# Interfaces.net
KiCad netlist of a schematic drawn in Altium Designer
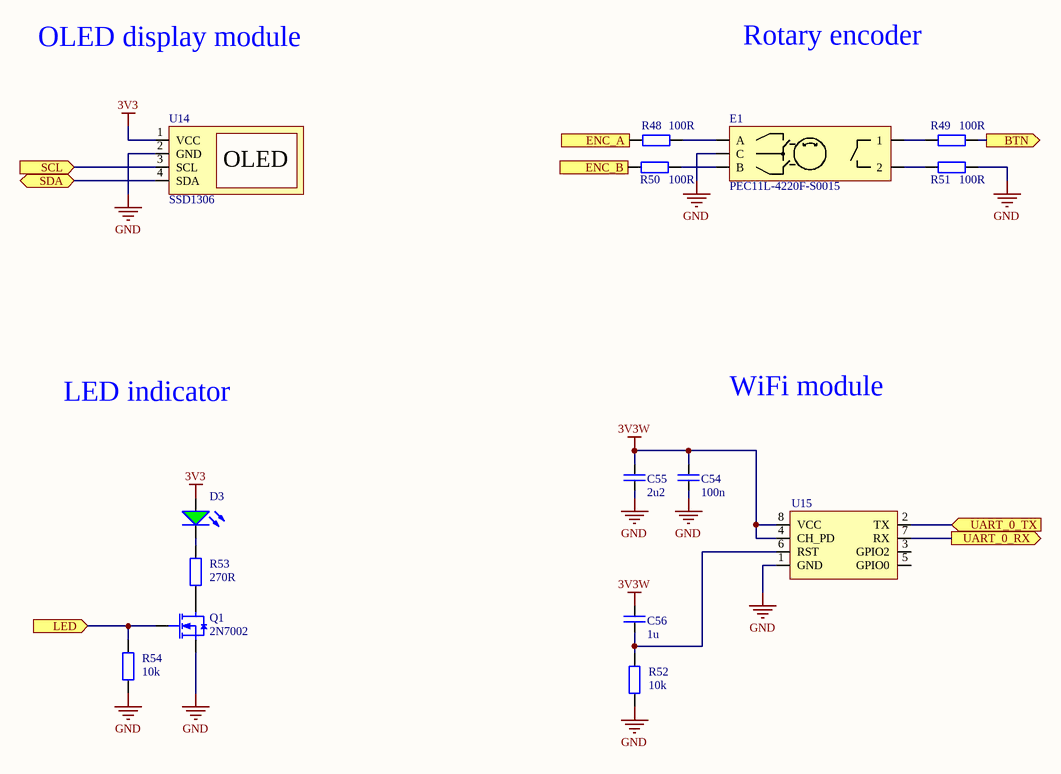
[diagram p0: Interfaces.SchDoc]

(export (version "E")
  (design (tool "Eeschema 10.0.6"))
  (components
    (comp (ref "C54")
      (value "100n")
      (footprint "C_0603")
      (description "Generic capacitor")
      (libsource (lib "DAQ") (part "Capacitor"))
    )
    (comp (ref "C55")
      (value "2u2")
      (footprint "C_0603")
      (description "Generic capacitor")
      (libsource (lib "DAQ") (part "Capacitor"))
    )
    (comp (ref "C56")
      (value "1u")
      (footprint "C_0603")
      (description "Generic capacitor")
      (libsource (lib "DAQ") (part "Capacitor"))
    )
    (comp (ref "D3")
      (value "LED Green")
      (footprint "LED_0603")
      (description "Generic LED Green")
      (libsource (lib "DAQ") (part "LED Green"))
    )
    (comp (ref "E1")
      (value "PEC11L-4220F-S0015")
      (footprint "PEC11L-4220F-S0015")
      (description "Low Profile Encoder 15 PPR 2 Bit Quadrature 5VDC at 10 mA IP40 PCB Mount")
      (fields (field (name "PART NUMBER") "XRE0000") (field (name "MANUFACTURER") "BOURNS"))
      (libsource (lib "DAQ") (part "PEC11L-4220F-S0015"))
    )
    (comp (ref "Q1")
      (value "2N7002")
      (footprint "SOT23-3")
      (description "60V 0.3A N-channel MOSFET")
      (fields (field (name "PART NUMBER") "XMN0002") (field (name "MANUFACTURER") "NXP"))
      (libsource (lib "DAQ") (part "2N7002"))
    )
    (comp (ref "R48")
      (value "100R")
      (footprint "R_0603")
      (description "Generic resistor")
      (fields (field (name "Comment") "comment"))
      (libsource (lib "DAQ") (part "Resistor"))
    )
    (comp (ref "R49")
      (value "100R")
      (footprint "R_0603")
      (description "Generic resistor")
      (fields (field (name "Comment") "comment"))
      (libsource (lib "DAQ") (part "Resistor"))
    )
    (comp (ref "R50")
      (value "100R")
      (footprint "R_0603")
      (description "Generic resistor")
      (fields (field (name "Comment") "comment"))
      (libsource (lib "DAQ") (part "Resistor"))
    )
    (comp (ref "R51")
      (value "100R")
      (footprint "R_0603")
      (description "Generic resistor")
      (fields (field (name "Comment") "comment"))
      (libsource (lib "DAQ") (part "Resistor"))
    )
    (comp (ref "R52")
      (value "10k")
      (footprint "R_0603")
      (description "Generic resistor")
      (fields (field (name "Comment") "comment"))
      (libsource (lib "DAQ") (part "Resistor"))
    )
    (comp (ref "R53")
      (value "270R")
      (footprint "R_0603")
      (description "Generic resistor")
      (fields (field (name "Comment") "comment"))
      (libsource (lib "DAQ") (part "Resistor"))
    )
    (comp (ref "R54")
      (value "10k")
      (footprint "R_0603")
      (description "Generic resistor")
      (fields (field (name "Comment") "comment"))
      (libsource (lib "DAQ") (part "Resistor"))
    )
    (comp (ref "U14")
      (value "SSD1306")
      (footprint "OLED1")
      (description "Oled display module")
      (fields (field (name "PART NUMBER") "OLM0000"))
      (libsource (lib "DAQ") (part "OLED_SSD1306"))
    )
    (comp (ref "U15")
      (value "ESP-01")
      (footprint "ESP-01")
      (description "WIFI module")
      (fields (field (name "PART NUMBER") "XWM0000"))
      (libsource (lib "DAQ") (part "ESP-01"))
    )
  )
  (nets
    (net (code "1") (name "/BTN") (class "Default") (node (ref "R49") (pin "2") (pintype "passive")))
    (net (code "2") (name "/ENC_A") (class "Default") (node (ref "R48") (pin "1") (pintype "passive")))
    (net (code "3") (name "/ENC_B") (class "Default") (node (ref "R50") (pin "1") (pintype "passive")))
    (net (code "4") (name "/LED") (class "Default")
      (node (ref "Q1") (pin "1") (pinfunction "G_1") (pintype "passive"))
      (node (ref "R54") (pin "2") (pintype "passive"))
    )
    (net (code "5") (name "/SCL") (class "Default")
      (node (ref "U14") (pin "3") (pinfunction "SCL_3") (pintype "passive"))
    )
    (net (code "6") (name "/SDA") (class "Default")
      (node (ref "U14") (pin "4") (pinfunction "SDA_4") (pintype "passive"))
    )
    (net (code "7") (name "/UART_0_RX") (class "Default")
      (node (ref "U15") (pin "7") (pinfunction "RX_7") (pintype "passive"))
    )
    (net (code "8") (name "/UART_0_TX") (class "Default")
      (node (ref "U15") (pin "2") (pinfunction "TX_2") (pintype "passive"))
    )
    (net (code "9") (name "3V3") (class "Default")
      (node (ref "D3") (pin "2") (pinfunction "+_2") (pintype "passive"))
      (node (ref "U14") (pin "1") (pinfunction "VCC_1") (pintype "passive"))
    )
    (net (code "10") (name "3V3W") (class "Default")
      (node (ref "C54") (pin "2") (pinfunction "2_2") (pintype "passive"))
      (node (ref "C55") (pin "2") (pinfunction "2_2") (pintype "passive"))
      (node (ref "C56") (pin "2") (pinfunction "2_2") (pintype "passive"))
      (node (ref "U15") (pin "4") (pinfunction "CH_PD_4") (pintype "passive"))
      (node (ref "U15") (pin "8") (pinfunction "VCC_8") (pintype "passive"))
    )
    (net (code "11") (name "GND") (class "Default")
      (node (ref "C54") (pin "1") (pinfunction "1_1") (pintype "passive"))
      (node (ref "C55") (pin "1") (pinfunction "1_1") (pintype "passive"))
      (node (ref "E1") (pin "C") (pinfunction "C_C") (pintype "passive"))
      (node (ref "Q1") (pin "2") (pinfunction "S_2") (pintype "passive"))
      (node (ref "R51") (pin "2") (pintype "passive"))
      (node (ref "R52") (pin "1") (pintype "passive"))
      (node (ref "R54") (pin "1") (pintype "passive"))
      (node (ref "U14") (pin "2") (pinfunction "GND_2") (pintype "passive"))
      (node (ref "U15") (pin "1") (pinfunction "GND_1") (pintype "passive"))
    )
    (net (code "12") (name "Net-(D3--)") (class "Default")
      (node (ref "D3") (pin "1") (pinfunction "-_1") (pintype "passive"))
      (node (ref "R53") (pin "2") (pintype "passive"))
    )
    (net (code "13") (name "Net-(E1-Pad1)") (class "Default")
      (node (ref "E1") (pin "1") (pinfunction "1_1") (pintype "passive"))
      (node (ref "R49") (pin "1") (pintype "passive"))
    )
    (net (code "14") (name "Net-(E1-Pad2)") (class "Default")
      (node (ref "E1") (pin "2") (pinfunction "2_2") (pintype "passive"))
      (node (ref "R51") (pin "1") (pintype "passive"))
    )
    (net (code "15") (name "Net-(E1-PadA)") (class "Default")
      (node (ref "E1") (pin "A") (pinfunction "A_A") (pintype "passive"))
      (node (ref "R48") (pin "2") (pintype "passive"))
    )
    (net (code "16") (name "Net-(E1-PadB)") (class "Default")
      (node (ref "E1") (pin "B") (pinfunction "B_B") (pintype "passive"))
      (node (ref "R50") (pin "2") (pintype "passive"))
    )
    (net (code "17") (name "Net-(Q1-D)") (class "Default")
      (node (ref "Q1") (pin "3") (pinfunction "D_3") (pintype "passive"))
      (node (ref "R53") (pin "1") (pintype "passive"))
    )
    (net (code "18") (name "Net-(U15-RST)") (class "Default")
      (node (ref "C56") (pin "1") (pinfunction "1_1") (pintype "passive"))
      (node (ref "R52") (pin "2") (pintype "passive"))
      (node (ref "U15") (pin "6") (pinfunction "RST_6") (pintype "passive"))
    )
    (net (code "19") (name "unconnected-(U15-GPIO0-Pad5)") (class "Default")
      (node (ref "U15") (pin "5") (pinfunction "GPIO0_5") (pintype "passive"))
    )
    (net (code "20") (name "unconnected-(U15-GPIO2-Pad3)") (class "Default")
      (node (ref "U15") (pin "3") (pinfunction "GPIO2_3") (pintype "passive"))
    )
  )
)
